# POWER.net
KiCad netlist of a schematic drawn in Altium Designer
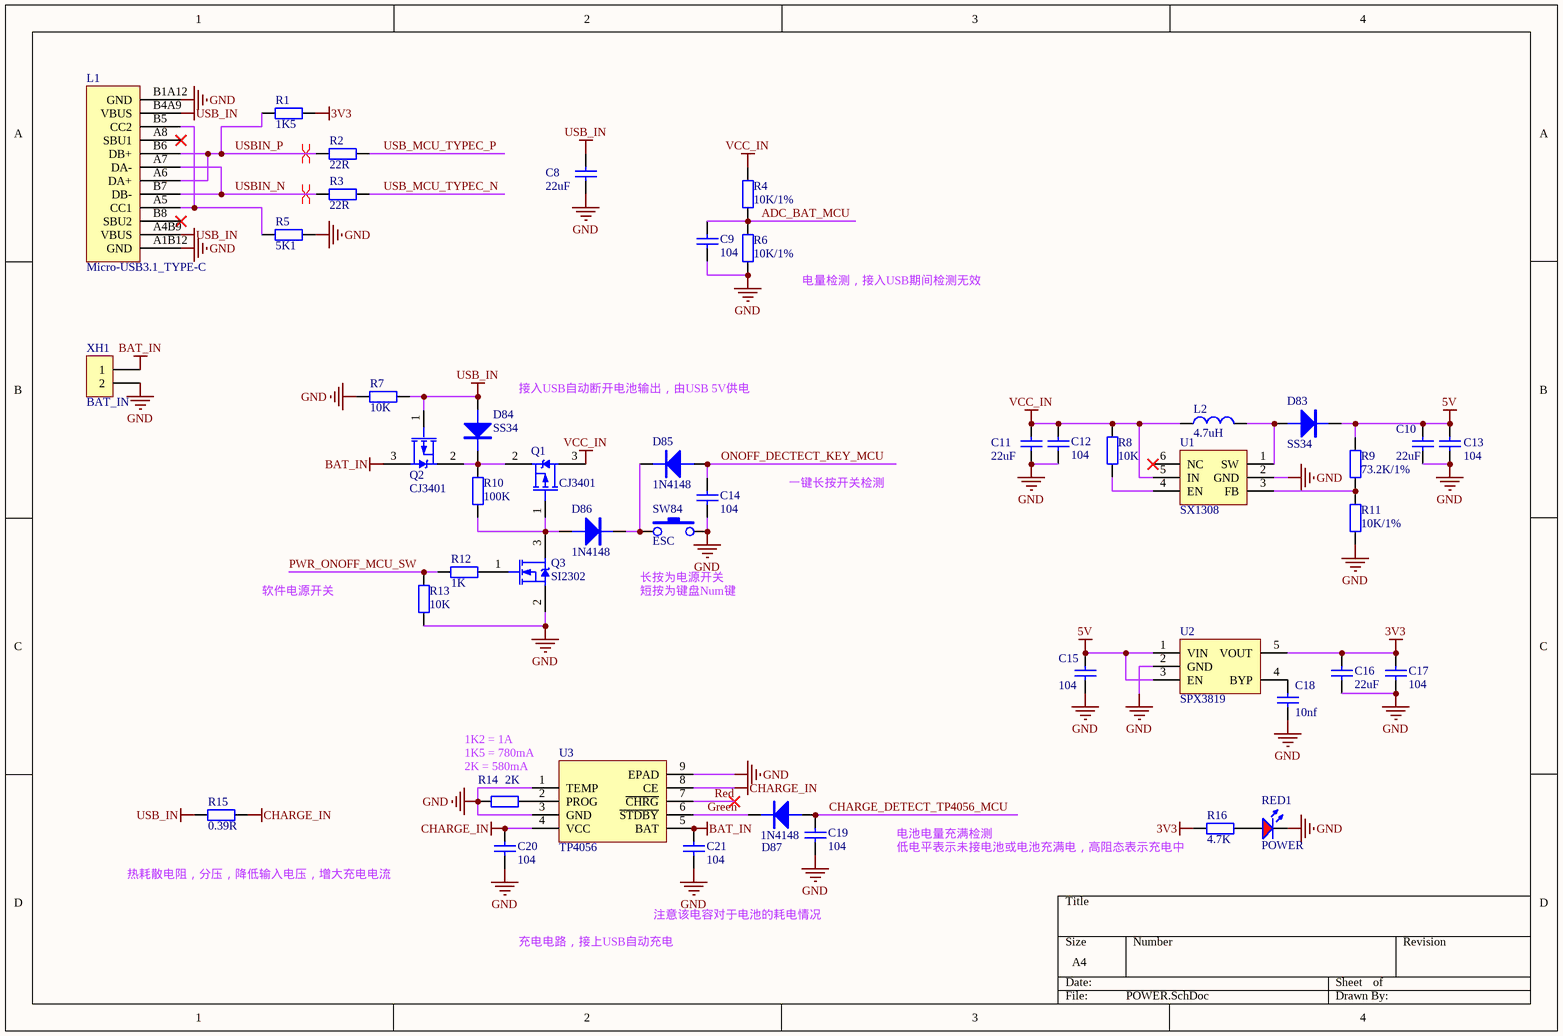
[diagram p0: POWER.SchDoc]

(export (version "E")
  (design (tool "Eeschema 10.0.6"))
  (components
    (comp (ref "C8")
      (value "22uF")
      (footprint "Cap-0805")
      (description "贴片陶瓷电容")
      (libsource (lib "Miscellaneous Base") (part "CAP"))
    )
    (comp (ref "C9")
      (value "104")
      (footprint "Cap-0603")
      (description "贴片陶瓷电容")
      (libsource (lib "Miscellaneous Base") (part "CAP"))
    )
    (comp (ref "C10")
      (value "22uF")
      (footprint "Cap-0805")
      (description "贴片陶瓷电容")
      (libsource (lib "Miscellaneous Base") (part "CAP"))
    )
    (comp (ref "C11")
      (value "22uF")
      (footprint "Cap-0805")
      (description "贴片陶瓷电容")
      (libsource (lib "Miscellaneous Base") (part "CAP"))
    )
    (comp (ref "C12")
      (value "104")
      (footprint "Cap-0603")
      (description "贴片陶瓷电容")
      (libsource (lib "Miscellaneous Base") (part "CAP"))
    )
    (comp (ref "C13")
      (value "104")
      (footprint "Cap-0603")
      (description "贴片陶瓷电容")
      (libsource (lib "Miscellaneous Base") (part "CAP"))
    )
    (comp (ref "C14")
      (value "104")
      (footprint "Cap-0603")
      (description "贴片陶瓷电容")
      (libsource (lib "Miscellaneous Base") (part "CAP"))
    )
    (comp (ref "C15")
      (value "104")
      (footprint "Cap-0603")
      (description "贴片陶瓷电容")
      (libsource (lib "Miscellaneous Base") (part "CAP"))
    )
    (comp (ref "C16")
      (value "22uF")
      (footprint "Cap-0805")
      (description "贴片陶瓷电容")
      (libsource (lib "Miscellaneous Base") (part "CAP"))
    )
    (comp (ref "C17")
      (value "104")
      (footprint "Cap-0603")
      (description "贴片陶瓷电容")
      (libsource (lib "Miscellaneous Base") (part "CAP"))
    )
    (comp (ref "C18") (value "10nf") (footprint "Cap-0603") (libsource (lib "base") (part "Cap")))
    (comp (ref "C19")
      (value "104")
      (footprint "Cap-0603")
      (description "贴片陶瓷电容")
      (libsource (lib "Miscellaneous Base") (part "CAP"))
    )
    (comp (ref "C20")
      (value "104")
      (footprint "Cap-0603")
      (description "贴片陶瓷电容")
      (libsource (lib "Miscellaneous Base") (part "CAP"))
    )
    (comp (ref "C21")
      (value "104")
      (footprint "Cap-0603")
      (description "贴片陶瓷电容")
      (libsource (lib "Miscellaneous Base") (part "CAP"))
    )
    (comp (ref "D83")
      (value "SS34")
      (footprint "Doide-SMA")
      (description "普通二极管")
      (libsource (lib "Miscellaneous Transistor") (part "DIODE"))
    )
    (comp (ref "D84")
      (value "SS34")
      (footprint "Doide-SMA")
      (description "普通二极管")
      (libsource (lib "Miscellaneous Transistor") (part "DIODE"))
    )
    (comp (ref "D85")
      (value "1N4148")
      (footprint "SOD-523")
      (description "普通二极管")
      (libsource (lib "Miscellaneous Transistor") (part "DIODE"))
    )
    (comp (ref "D86")
      (value "1N4148")
      (footprint "SOD-523")
      (description "普通二极管")
      (libsource (lib "Miscellaneous Transistor") (part "DIODE"))
    )
    (comp (ref "D87")
      (value "1N4148")
      (footprint "SOD-523")
      (description "普通二极管")
      (libsource (lib "Miscellaneous Transistor") (part "DIODE"))
    )
    (comp (ref "L1")
      (value "Micro-USB3.1_TYPE-C")
      (footprint "USB3.0-TYPEC-12P")
      (libsource (lib "Miscellaneous Socket") (part "Micro-USB3.1_TYPE-C"))
    )
    (comp (ref "L2")
      (value "4.7uH")
      (footprint "L-MHC0603")
      (description "贴片屏蔽电感")
      (libsource (lib "Miscellaneous Base") (part "INDUCTOR-SMD"))
    )
    (comp (ref "Q1")
      (value "CJ3401")
      (footprint "SOT23-3")
      (description "P-Channel MOSFET")
      (fields (field (name "PUBLISHER") "Altium Limited"))
      (libsource (lib "Miscellaneous Transistor") (part "MOSFET-P2"))
    )
    (comp (ref "Q2")
      (value "CJ3401")
      (footprint "SOT23-3")
      (description "P-Channel MOSFET")
      (fields (field (name "PUBLISHER") "Altium Limited"))
      (libsource (lib "Miscellaneous Transistor") (part "MOSFET-P2"))
    )
    (comp (ref "Q3")
      (value "SI2302")
      (footprint "SOT23-3")
      (description "N-Channel MOSFET")
      (fields (field (name "PUBLISHER") "Altium Limited"))
      (libsource (lib "Miscellaneous Transistor") (part "MOSFET-N2"))
    )
    (comp (ref "R1")
      (value "1K5")
      (footprint "Res-0603")
      (description "贴片电阻")
      (libsource (lib "") (part "RES_1"))
    )
    (comp (ref "R2")
      (value "22R")
      (footprint "Res-0603")
      (description "贴片电阻")
      (libsource (lib "") (part "RES_1"))
    )
    (comp (ref "R3")
      (value "22R")
      (footprint "Res-0603")
      (description "贴片电阻")
      (libsource (lib "") (part "RES_1"))
    )
    (comp (ref "R4")
      (value "10K/1%")
      (footprint "Res-0603")
      (description "贴片电阻")
      (libsource (lib "") (part "RES_2"))
    )
    (comp (ref "R5")
      (value "5K1")
      (footprint "Res-0603")
      (description "贴片电阻")
      (libsource (lib "") (part "RES_1"))
    )
    (comp (ref "R6")
      (value "10K/1%")
      (footprint "Res-0603")
      (description "贴片电阻")
      (libsource (lib "") (part "RES_2"))
    )
    (comp (ref "R7")
      (value "10K")
      (footprint "Res-0603")
      (description "贴片电阻")
      (libsource (lib "") (part "RES_1"))
    )
    (comp (ref "R8")
      (value "10K")
      (footprint "Res-0603")
      (description "贴片电阻")
      (libsource (lib "") (part "RES_1"))
    )
    (comp (ref "R9")
      (value "73.2K/1%")
      (footprint "Res-0603")
      (description "贴片电阻")
      (libsource (lib "Miscellaneous Base") (part "RES"))
    )
    (comp (ref "R10")
      (value "100K")
      (footprint "Res-0603")
      (description "贴片电阻")
      (libsource (lib "") (part "RES_3"))
    )
    (comp (ref "R11")
      (value "10K/1%")
      (footprint "Res-0603")
      (description "贴片电阻")
      (libsource (lib "Miscellaneous Base") (part "RES"))
    )
    (comp (ref "R12")
      (value "1K")
      (footprint "Res-0603")
      (description "贴片电阻")
      (libsource (lib "Miscellaneous Base") (part "RES"))
    )
    (comp (ref "R13")
      (value "10K")
      (footprint "Res-0603")
      (description "贴片电阻")
      (libsource (lib "") (part "RES_3"))
    )
    (comp (ref "R14")
      (value "2K")
      (footprint "Res-0603")
      (description "贴片电阻")
      (libsource (lib "") (part "RES_1"))
    )
    (comp (ref "R15")
      (value "0.39R")
      (footprint "Res-1812")
      (description "贴片电阻")
      (libsource (lib "Miscellaneous Base") (part "RES"))
    )
    (comp (ref "R16")
      (value "4.7K")
      (footprint "Res-0603")
      (description "贴片电阻")
      (libsource (lib "") (part "RES_1"))
    )
    (comp (ref "RED1")
      (value "POWER")
      (footprint "LED_0603_R")
      (description "发光二极管")
      (libsource (lib "Miscellaneous Transistor") (part "LED_SMD_RED"))
    )
    (comp (ref "SW84")
      (value "ESC")
      (footprint "MX_SW-4")
      (description "with Fixation pins  1-Pole")
      (libsource (lib "KeyBoard_rebacha") (part "MX_SW-4"))
    )
    (comp (ref "U1")
      (value "SX1308")
      (footprint "SX1308")
      (libsource (lib "Miscellaneous PMIC") (part "SX1308"))
    )
    (comp (ref "U2")
      (value "SPX3819")
      (footprint "SOT23-5")
      (libsource (lib "Miscellaneous PMIC") (part "SPX3819"))
    )
    (comp (ref "U3")
      (value "TP4056")
      (footprint "TP4056")
      (libsource (lib "Miscellaneous PMIC") (part "tp4056"))
    )
    (comp (ref "XH1") (value "BAT_IN") (footprint "XH2/2.54mm/180") (libsource (lib "XH，VH") (part "XH2")))
  )
  (nets
    (net (code "1") (name "/ADC_BAT_MCU") (class "Default")
      (node (ref "C9") (pin "2") (pinfunction "2_2") (pintype "passive"))
      (node (ref "R4") (pin "1") (pinfunction "1_1") (pintype "passive"))
      (node (ref "R6") (pin "2") (pinfunction "2_2") (pintype "passive"))
    )
    (net (code "2") (name "/CHARGE_DETECT_TP4056_MCU") (class "Default")
      (node (ref "C19") (pin "2") (pinfunction "2_2") (pintype "passive"))
      (node (ref "D87") (pin "A") (pinfunction "A_A") (pintype "passive"))
    )
    (net (code "3") (name "/Green") (class "Default")
      (node (ref "D87") (pin "K") (pinfunction "K_K") (pintype "passive"))
      (node (ref "U3") (pin "6") (pinfunction "~{STDBY}_6") (pintype "passive"))
    )
    (net (code "4") (name "/ONOFF_DECTECT_KEY_MCU") (class "Default")
      (node (ref "C14") (pin "1") (pinfunction "1_1") (pintype "passive"))
      (node (ref "D85") (pin "A") (pinfunction "A_A") (pintype "passive"))
    )
    (net (code "5") (name "/PWR_ONOFF_MCU_SW") (class "Default")
      (node (ref "R12") (pin "1") (pinfunction "1_1") (pintype "passive"))
      (node (ref "R13") (pin "1") (pinfunction "1_1") (pintype "passive"))
    )
    (net (code "6") (name "/Red") (class "Default")
      (node (ref "U3") (pin "7") (pinfunction "~{CHRG}_7") (pintype "passive+no_connect"))
    )
    (net (code "7") (name "/USBIN_N") (class "Default")
      (node (ref "L1") (pin "A7") (pinfunction "DA-_A7") (pintype "passive"))
      (node (ref "L1") (pin "B7") (pinfunction "DB-_B7") (pintype "passive"))
      (node (ref "R3") (pin "2") (pinfunction "2_2") (pintype "passive"))
    )
    (net (code "8") (name "/USBIN_P") (class "Default")
      (node (ref "L1") (pin "A6") (pinfunction "DA+_A6") (pintype "passive"))
      (node (ref "L1") (pin "B6") (pinfunction "DB+_B6") (pintype "passive"))
      (node (ref "R1") (pin "2") (pinfunction "2_2") (pintype "passive"))
      (node (ref "R2") (pin "2") (pinfunction "2_2") (pintype "passive"))
    )
    (net (code "9") (name "/USB_MCU_TYPEC_N") (class "Default")
      (node (ref "R3") (pin "1") (pinfunction "1_1") (pintype "passive"))
    )
    (net (code "10") (name "/USB_MCU_TYPEC_P") (class "Default")
      (node (ref "R2") (pin "1") (pinfunction "1_1") (pintype "passive"))
    )
    (net (code "11") (name "3V3") (class "Default")
      (node (ref "C16") (pin "2") (pinfunction "2_2") (pintype "passive"))
      (node (ref "C17") (pin "1") (pinfunction "1_1") (pintype "passive"))
      (node (ref "R1") (pin "1") (pinfunction "1_1") (pintype "passive"))
      (node (ref "R16") (pin "2") (pinfunction "2_2") (pintype "passive"))
      (node (ref "U2") (pin "5") (pinfunction "VOUT_5") (pintype "power_in"))
    )
    (net (code "12") (name "5V") (class "Default")
      (node (ref "C10") (pin "2") (pinfunction "2_2") (pintype "passive"))
      (node (ref "C13") (pin "2") (pinfunction "2_2") (pintype "passive"))
      (node (ref "C15") (pin "2") (pinfunction "2_2") (pintype "passive"))
      (node (ref "D83") (pin "K") (pinfunction "K_K") (pintype "passive"))
      (node (ref "R9") (pin "2") (pinfunction "2_2") (pintype "passive"))
      (node (ref "U2") (pin "1") (pinfunction "VIN_1") (pintype "power_in"))
      (node (ref "U2") (pin "3") (pinfunction "EN_3") (pintype "power_in"))
    )
    (net (code "13") (name "BAT_IN") (class "Default")
      (node (ref "C21") (pin "2") (pinfunction "2_2") (pintype "passive"))
      (node (ref "Q2") (pin "3") (pinfunction "D_3") (pintype "passive"))
      (node (ref "U3") (pin "5") (pinfunction "BAT_5") (pintype "passive"))
      (node (ref "XH1") (pin "1") (pinfunction "1_1") (pintype "passive"))
    )
    (net (code "14") (name "CHARGE_IN") (class "Default")
      (node (ref "C20") (pin "2") (pinfunction "2_2") (pintype "passive"))
      (node (ref "R15") (pin "2") (pinfunction "2_2") (pintype "passive"))
      (node (ref "U3") (pin "4") (pinfunction "VCC_4") (pintype "passive"))
      (node (ref "U3") (pin "8") (pinfunction "CE_8") (pintype "passive"))
    )
    (net (code "15") (name "GND") (class "Default")
      (node (ref "C10") (pin "1") (pinfunction "1_1") (pintype "passive"))
      (node (ref "C11") (pin "1") (pinfunction "1_1") (pintype "passive"))
      (node (ref "C12") (pin "1") (pinfunction "1_1") (pintype "passive"))
      (node (ref "C13") (pin "1") (pinfunction "1_1") (pintype "passive"))
      (node (ref "C14") (pin "2") (pinfunction "2_2") (pintype "passive"))
      (node (ref "C15") (pin "1") (pinfunction "1_1") (pintype "passive"))
      (node (ref "C16") (pin "1") (pinfunction "1_1") (pintype "passive"))
      (node (ref "C17") (pin "2") (pinfunction "2_2") (pintype "passive"))
      (node (ref "C18") (pin "1") (pinfunction "1_1") (pintype "passive"))
      (node (ref "C19") (pin "1") (pinfunction "1_1") (pintype "passive"))
      (node (ref "C20") (pin "1") (pinfunction "1_1") (pintype "passive"))
      (node (ref "C21") (pin "1") (pinfunction "1_1") (pintype "passive"))
      (node (ref "C8") (pin "1") (pinfunction "1_1") (pintype "passive"))
      (node (ref "C9") (pin "1") (pinfunction "1_1") (pintype "passive"))
      (node (ref "L1") (pin "A1B12") (pinfunction "GND_A1B12") (pintype "passive"))
      (node (ref "L1") (pin "B1A12") (pinfunction "GND_B1A12") (pintype "passive"))
      (node (ref "Q3") (pin "2") (pinfunction "S_2") (pintype "passive"))
      (node (ref "R11") (pin "1") (pinfunction "1_1") (pintype "passive"))
      (node (ref "R13") (pin "2") (pinfunction "2_2") (pintype "passive"))
      (node (ref "R14") (pin "2") (pinfunction "2_2") (pintype "passive"))
      (node (ref "R5") (pin "1") (pinfunction "1_1") (pintype "passive"))
      (node (ref "R6") (pin "1") (pinfunction "1_1") (pintype "passive"))
      (node (ref "R7") (pin "2") (pinfunction "2_2") (pintype "passive"))
      (node (ref "RED1") (pin "2") (pinfunction "K_2") (pintype "passive"))
      (node (ref "SW84") (pin "2") (pinfunction "2_2") (pintype "passive"))
      (node (ref "U1") (pin "2") (pinfunction "GND_2") (pintype "passive"))
      (node (ref "U2") (pin "2") (pinfunction "GND_2") (pintype "power_in"))
      (node (ref "U3") (pin "1") (pinfunction "TEMP_1") (pintype "passive"))
      (node (ref "U3") (pin "3") (pinfunction "GND_3") (pintype "passive"))
      (node (ref "U3") (pin "9") (pinfunction "EPAD_9") (pintype "passive"))
      (node (ref "XH1") (pin "2") (pinfunction "2_2") (pintype "passive"))
    )
    (net (code "16") (name "Net-(D85-PadK)") (class "Default")
      (node (ref "D85") (pin "K") (pinfunction "K_K") (pintype "passive"))
      (node (ref "D86") (pin "K") (pinfunction "K_K") (pintype "passive"))
      (node (ref "SW84") (pin "1") (pinfunction "1_1") (pintype "passive"))
    )
    (net (code "17") (name "Net-(L1-CC1)") (class "Default")
      (node (ref "L1") (pin "A5") (pinfunction "CC1_A5") (pintype "passive"))
      (node (ref "L1") (pin "B5") (pinfunction "CC2_B5") (pintype "passive"))
      (node (ref "R5") (pin "2") (pinfunction "2_2") (pintype "passive"))
    )
    (net (code "18") (name "Net-(Q1-G)") (class "Default")
      (node (ref "D86") (pin "A") (pinfunction "A_A") (pintype "passive"))
      (node (ref "Q1") (pin "1") (pinfunction "G_1") (pintype "passive"))
      (node (ref "Q3") (pin "3") (pinfunction "D_3") (pintype "passive"))
      (node (ref "R10") (pin "2") (pinfunction "2_2") (pintype "passive"))
    )
    (net (code "19") (name "Net-(Q1-S)") (class "Default")
      (node (ref "D84") (pin "K") (pinfunction "K_K") (pintype "passive"))
      (node (ref "Q1") (pin "2") (pinfunction "S_2") (pintype "passive"))
      (node (ref "Q2") (pin "2") (pinfunction "S_2") (pintype "passive"))
      (node (ref "R10") (pin "1") (pinfunction "1_1") (pintype "passive"))
    )
    (net (code "20") (name "Net-(Q3-G)") (class "Default")
      (node (ref "Q3") (pin "1") (pinfunction "G_1") (pintype "passive"))
      (node (ref "R12") (pin "2") (pinfunction "2_2") (pintype "passive"))
    )
    (net (code "21") (name "Net-(RED1-A)") (class "Default")
      (node (ref "R16") (pin "1") (pinfunction "1_1") (pintype "passive"))
      (node (ref "RED1") (pin "1") (pinfunction "A_1") (pintype "passive"))
    )
    (net (code "22") (name "Net-(U1-EN)") (class "Default")
      (node (ref "R8") (pin "2") (pinfunction "2_2") (pintype "passive"))
      (node (ref "U1") (pin "4") (pinfunction "EN_4") (pintype "passive"))
    )
    (net (code "23") (name "Net-(U1-FB)") (class "Default")
      (node (ref "R11") (pin "2") (pinfunction "2_2") (pintype "passive"))
      (node (ref "R9") (pin "1") (pinfunction "1_1") (pintype "passive"))
      (node (ref "U1") (pin "3") (pinfunction "FB_3") (pintype "passive"))
    )
    (net (code "24") (name "Net-(U1-SW)") (class "Default")
      (node (ref "D83") (pin "A") (pinfunction "A_A") (pintype "passive"))
      (node (ref "L2") (pin "1") (pinfunction "1_1") (pintype "passive"))
      (node (ref "U1") (pin "1") (pinfunction "SW_1") (pintype "passive"))
    )
    (net (code "25") (name "Net-(U2-BYP)") (class "Default")
      (node (ref "C18") (pin "2") (pinfunction "2_2") (pintype "passive"))
      (node (ref "U2") (pin "4") (pinfunction "BYP_4") (pintype "power_in"))
    )
    (net (code "26") (name "Net-(U3-PROG)") (class "Default")
      (node (ref "R14") (pin "1") (pinfunction "1_1") (pintype "passive"))
      (node (ref "U3") (pin "2") (pinfunction "PROG_2") (pintype "passive"))
    )
    (net (code "27") (name "USB_IN") (class "Default")
      (node (ref "C8") (pin "2") (pinfunction "2_2") (pintype "passive"))
      (node (ref "D84") (pin "A") (pinfunction "A_A") (pintype "passive"))
      (node (ref "L1") (pin "A4B9") (pinfunction "VBUS_A4B9") (pintype "passive"))
      (node (ref "L1") (pin "B4A9") (pinfunction "VBUS_B4A9") (pintype "passive"))
      (node (ref "Q2") (pin "1") (pinfunction "G_1") (pintype "passive"))
      (node (ref "R15") (pin "1") (pinfunction "1_1") (pintype "passive"))
      (node (ref "R7") (pin "1") (pinfunction "1_1") (pintype "passive"))
    )
    (net (code "28") (name "VCC_IN") (class "Default")
      (node (ref "C11") (pin "2") (pinfunction "2_2") (pintype "passive"))
      (node (ref "C12") (pin "2") (pinfunction "2_2") (pintype "passive"))
      (node (ref "L2") (pin "2") (pinfunction "2_2") (pintype "passive"))
      (node (ref "Q1") (pin "3") (pinfunction "D_3") (pintype "passive"))
      (node (ref "R4") (pin "2") (pinfunction "2_2") (pintype "passive"))
      (node (ref "R8") (pin "1") (pinfunction "1_1") (pintype "passive"))
      (node (ref "U1") (pin "5") (pinfunction "IN_5") (pintype "passive"))
    )
    (net (code "29") (name "unconnected-(L1-SBU1-PadA8)") (class "Default")
      (node (ref "L1") (pin "A8") (pinfunction "SBU1_A8") (pintype "passive+no_connect"))
    )
    (net (code "30") (name "unconnected-(L1-SBU2-PadB8)") (class "Default")
      (node (ref "L1") (pin "B8") (pinfunction "SBU2_B8") (pintype "passive+no_connect"))
    )
    (net (code "31") (name "unconnected-(U1-NC-Pad6)") (class "Default")
      (node (ref "U1") (pin "6") (pinfunction "NC_6") (pintype "passive+no_connect"))
    )
  )
)
